# PonyProgFT.net
KiCad netlist of a schematic drawn in Altium Designer
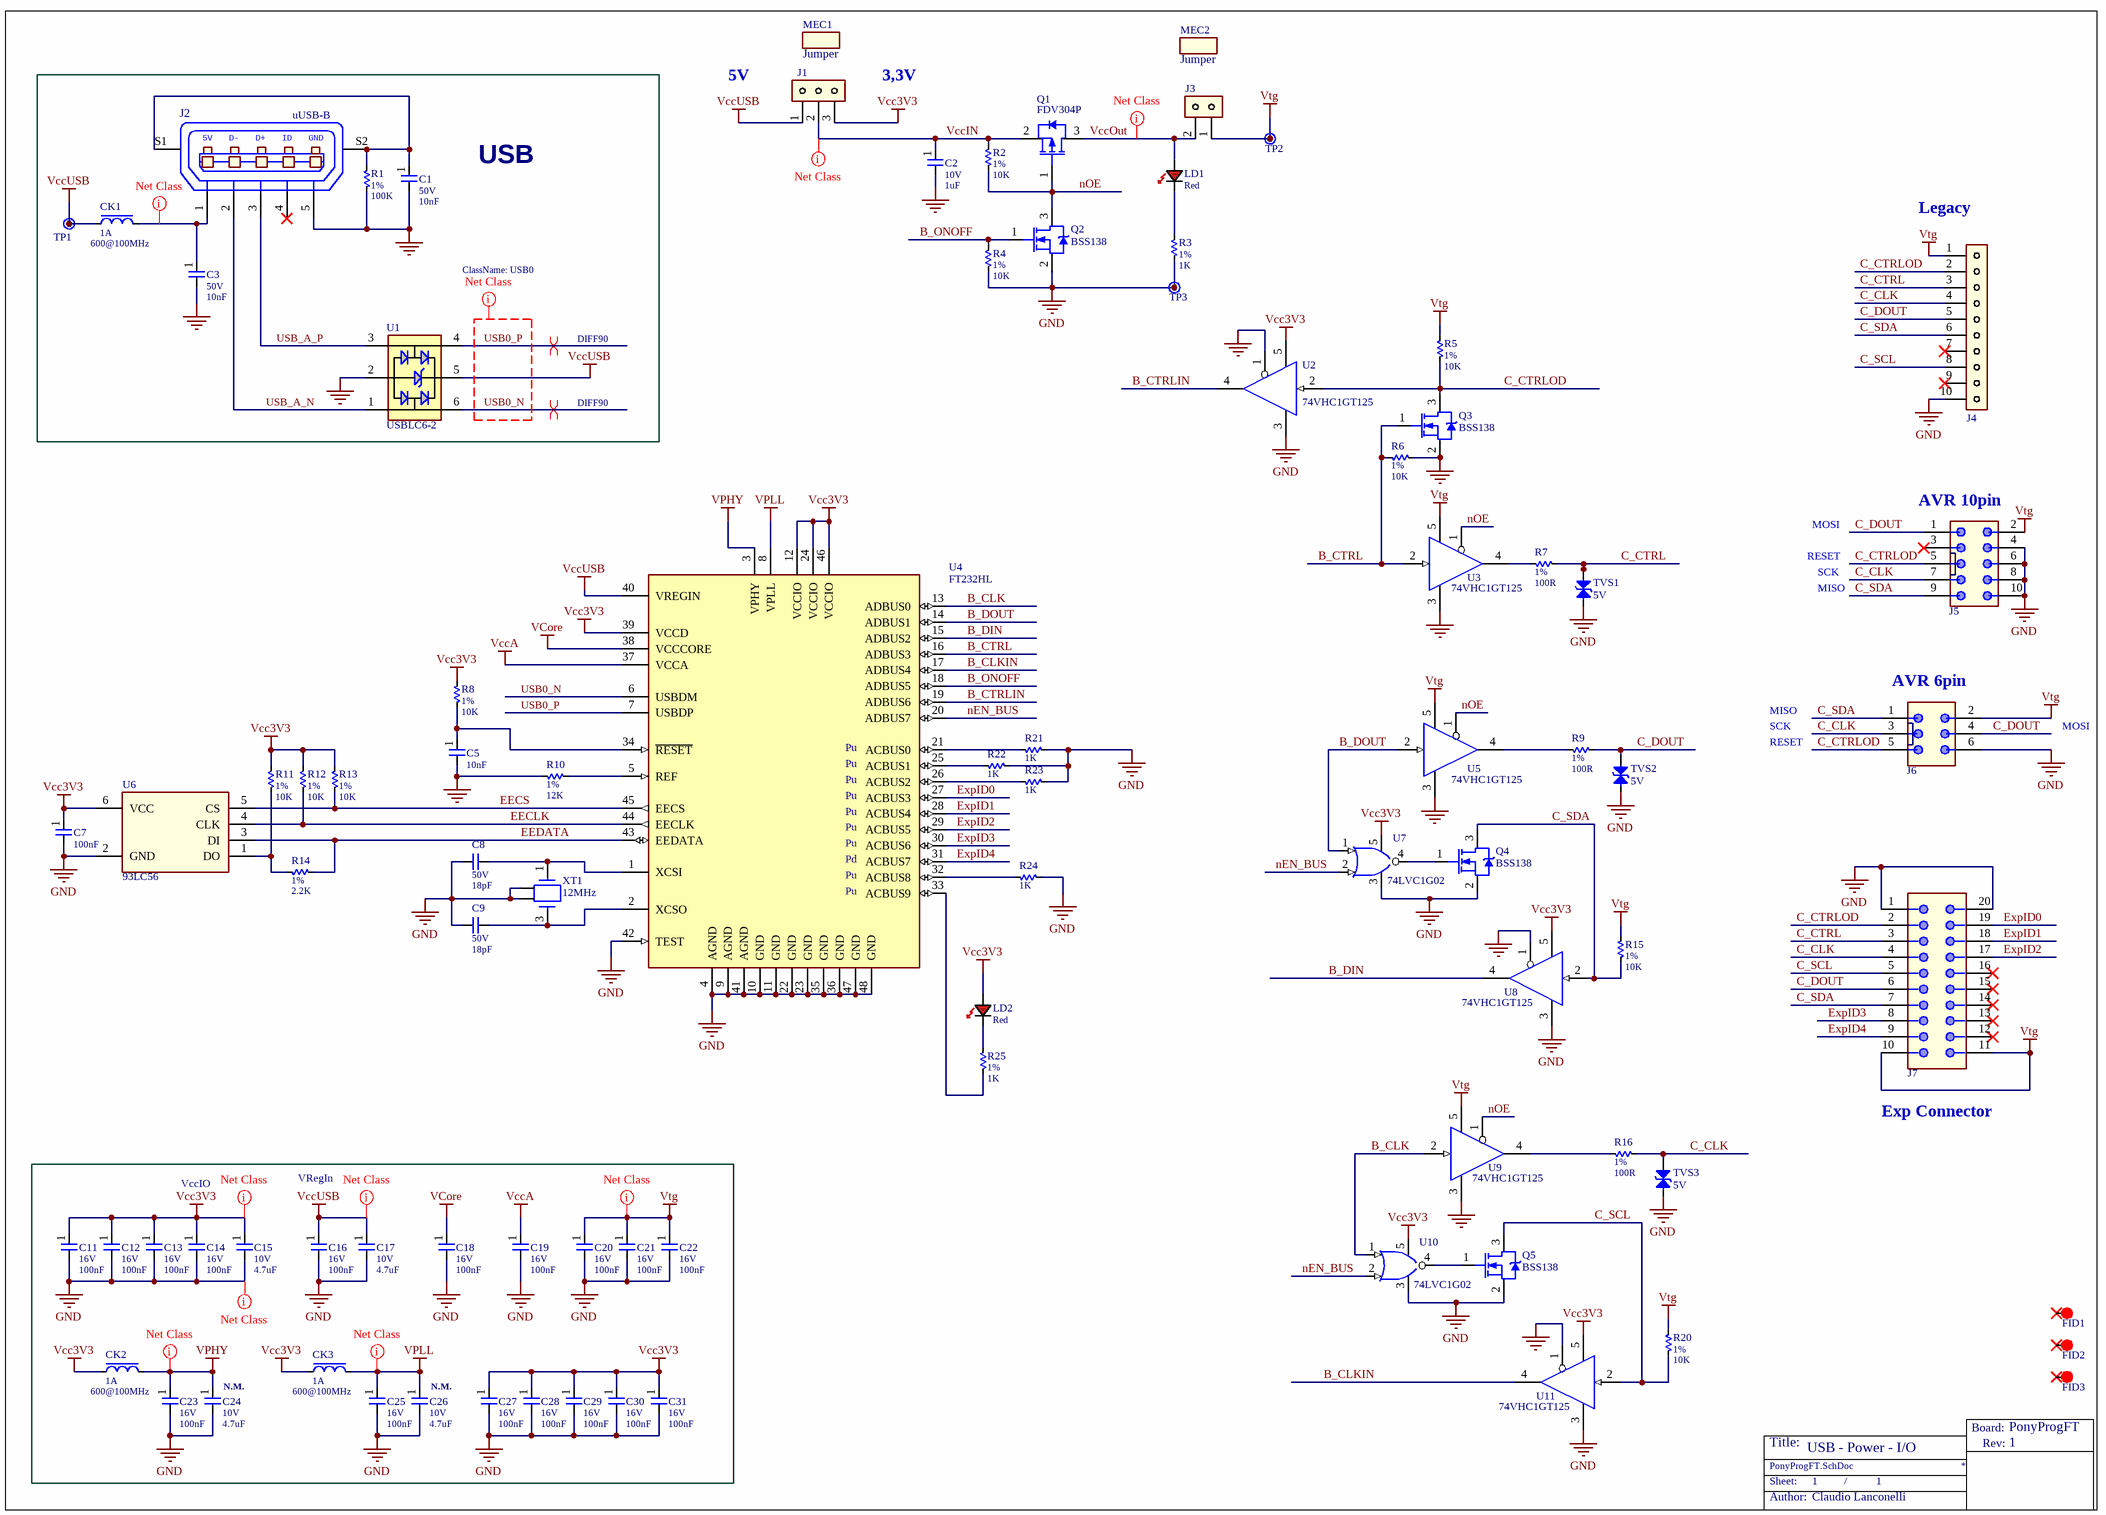
[diagram p0: PonyProgFT.SchDoc]

(export (version "E")
  (design (tool "Eeschema 10.0.6"))
  (components
    (comp (ref "C1")
      (value "10nF")
      (footprint "C0805_M")
      (description "Chip Ceramic Capacitor X7R 0805 10nF 50V 10%")
      (fields
        (field (name "TOLERANCE") "10%")
        (field (name "MANUFACTURER") "Samsung Electro-Mechanics")
        (field (name "VOLTAGE") "50V")
      )
      (libsource (lib "LancoLib") (part "CX7R10N50V10%0805_CL"))
    )
    (comp (ref "C2")
      (value "1uF")
      (footprint "C0603_M")
      (description "Chip Ceramic Capacitor X5R 0603 1uF 10V 10%")
      (fields
        (field (name "TOLERANCE") "10%")
        (field (name "MANUFACTURER") "Murata Electronics North America")
        (field (name "VOLTAGE") "10V")
      )
      (libsource (lib "LancoLib") (part "CX5R1U10V10%0603_GRM"))
    )
    (comp (ref "C3")
      (value "10nF")
      (footprint "C0805_M")
      (description "Chip Ceramic Capacitor X7R 0805 10nF 50V 10%")
      (fields
        (field (name "TOLERANCE") "10%")
        (field (name "MANUFACTURER") "Samsung Electro-Mechanics")
        (field (name "VOLTAGE") "50V")
      )
      (libsource (lib "LancoLib") (part "CX7R10N50V10%0805_CL"))
    )
    (comp (ref "C5")
      (value "10nF")
      (footprint "C0402_H")
      (description "Chip Ceramic Capacitor X7R 0402 10nF 25V 10%")
      (fields
        (field (name "TOLERANCE") "10%")
        (field (name "MANUFACTURER") "Murata Electronics North America")
      )
      (libsource (lib "LancoLib") (part "CX7R10N25V10%0402_GRM"))
    )
    (comp (ref "C7")
      (value "100nF")
      (footprint "C0402_H")
      (description "Chip Ceramic Capacitor X7R 0402 100nF 16V 10%")
      (fields
        (field (name "TOLERANCE") "10%")
        (field (name "MANUFACTURER") "Murata Electronics North America")
      )
      (libsource (lib "LancoLib") (part "CX7R100N16V10%0402_GRM"))
    )
    (comp (ref "C8")
      (value "18pF")
      (footprint "C0603_M")
      (description "Chip Ceramic Capacitor C0G 0603 18pF 50V 5%")
      (fields
        (field (name "TOLERANCE") "5%")
        (field (name "VOLTAGE") "50V")
        (field (name "MANUFACTURER") "Kemet")
      )
      (libsource (lib "LancoLib") (part "CCOG18P50V5%0603_KEMET"))
    )
    (comp (ref "C9")
      (value "18pF")
      (footprint "C0603_M")
      (description "Chip Ceramic Capacitor C0G 0603 18pF 50V 5%")
      (fields
        (field (name "TOLERANCE") "5%")
        (field (name "VOLTAGE") "50V")
        (field (name "MANUFACTURER") "Kemet")
      )
      (libsource (lib "LancoLib") (part "CCOG18P50V5%0603_KEMET"))
    )
    (comp (ref "C11")
      (value "100nF")
      (footprint "C0402_H")
      (description "Chip Ceramic Capacitor X7R 0402 100nF 16V 10%")
      (fields
        (field (name "TOLERANCE") "10%")
        (field (name "MANUFACTURER") "Murata Electronics North America")
        (field (name "VOLTAGE") "16V")
      )
      (libsource (lib "LancoLib") (part "CX7R100N16V10%0402_GRM"))
    )
    (comp (ref "C12")
      (value "100nF")
      (footprint "C0402_H")
      (description "Chip Ceramic Capacitor X7R 0402 100nF 16V 10%")
      (fields
        (field (name "TOLERANCE") "10%")
        (field (name "MANUFACTURER") "Murata Electronics North America")
        (field (name "VOLTAGE") "16V")
      )
      (libsource (lib "LancoLib") (part "CX7R100N16V10%0402_GRM"))
    )
    (comp (ref "C13")
      (value "100nF")
      (footprint "C0402_H")
      (description "Chip Ceramic Capacitor X7R 0402 100nF 16V 10%")
      (fields
        (field (name "TOLERANCE") "10%")
        (field (name "MANUFACTURER") "Murata Electronics North America")
        (field (name "VOLTAGE") "16V")
      )
      (libsource (lib "LancoLib") (part "CX7R100N16V10%0402_GRM"))
    )
    (comp (ref "C14")
      (value "100nF")
      (footprint "C0402_H")
      (description "Chip Ceramic Capacitor X7R 0402 100nF 16V 10%")
      (fields
        (field (name "TOLERANCE") "10%")
        (field (name "MANUFACTURER") "Murata Electronics North America")
        (field (name "VOLTAGE") "16V")
      )
      (libsource (lib "LancoLib") (part "CX7R100N16V10%0402_GRM"))
    )
    (comp (ref "C15")
      (value "4.7uF")
      (footprint "C0603_H")
      (description "Chip Ceramic Capacitor X5R 0603 4.7uF 10V 10%")
      (fields
        (field (name "TOLERANCE") "10%")
        (field (name "MANUFACTURER") "TDK Corporation")
        (field (name "VOLTAGE") "10V")
      )
      (libsource (lib "LancoLib") (part "CX5R4.7U10V10%0603_TDK"))
    )
    (comp (ref "C16")
      (value "100nF")
      (footprint "C0402_H")
      (description "Chip Ceramic Capacitor X7R 0402 100nF 16V 10%")
      (fields
        (field (name "TOLERANCE") "10%")
        (field (name "MANUFACTURER") "Murata Electronics North America")
        (field (name "VOLTAGE") "16V")
      )
      (libsource (lib "LancoLib") (part "CX7R100N16V10%0402_GRM"))
    )
    (comp (ref "C17")
      (value "4.7uF")
      (footprint "C0603_H")
      (description "Chip Ceramic Capacitor X5R 0603 4.7uF 10V 10%")
      (fields
        (field (name "TOLERANCE") "10%")
        (field (name "MANUFACTURER") "TDK Corporation")
        (field (name "VOLTAGE") "10V")
      )
      (libsource (lib "LancoLib") (part "CX5R4.7U10V10%0603_TDK"))
    )
    (comp (ref "C18")
      (value "100nF")
      (footprint "C0402_H")
      (description "Chip Ceramic Capacitor X7R 0402 100nF 16V 10%")
      (fields
        (field (name "TOLERANCE") "10%")
        (field (name "MANUFACTURER") "Murata Electronics North America")
        (field (name "VOLTAGE") "16V")
      )
      (libsource (lib "LancoLib") (part "CX7R100N16V10%0402_GRM"))
    )
    (comp (ref "C19")
      (value "100nF")
      (footprint "C0402_H")
      (description "Chip Ceramic Capacitor X7R 0402 100nF 16V 10%")
      (fields
        (field (name "TOLERANCE") "10%")
        (field (name "MANUFACTURER") "Murata Electronics North America")
        (field (name "VOLTAGE") "16V")
      )
      (libsource (lib "LancoLib") (part "CX7R100N16V10%0402_GRM"))
    )
    (comp (ref "C20")
      (value "100nF")
      (footprint "C0402_H")
      (description "Chip Ceramic Capacitor X7R 0402 100nF 16V 10%")
      (fields
        (field (name "TOLERANCE") "10%")
        (field (name "MANUFACTURER") "Murata Electronics North America")
        (field (name "VOLTAGE") "16V")
      )
      (libsource (lib "LancoLib") (part "CX7R100N16V10%0402_GRM"))
    )
    (comp (ref "C21")
      (value "100nF")
      (footprint "C0402_H")
      (description "Chip Ceramic Capacitor X7R 0402 100nF 16V 10%")
      (fields
        (field (name "TOLERANCE") "10%")
        (field (name "MANUFACTURER") "Murata Electronics North America")
        (field (name "VOLTAGE") "16V")
      )
      (libsource (lib "LancoLib") (part "CX7R100N16V10%0402_GRM"))
    )
    (comp (ref "C22")
      (value "100nF")
      (footprint "C0402_H")
      (description "Chip Ceramic Capacitor X7R 0402 100nF 16V 10%")
      (fields
        (field (name "TOLERANCE") "10%")
        (field (name "MANUFACTURER") "Murata Electronics North America")
        (field (name "VOLTAGE") "16V")
      )
      (libsource (lib "LancoLib") (part "CX7R100N16V10%0402_GRM"))
    )
    (comp (ref "C23")
      (value "100nF")
      (footprint "C0402_H")
      (description "Chip Ceramic Capacitor X7R 0402 100nF 16V 10%")
      (fields
        (field (name "TOLERANCE") "10%")
        (field (name "MANUFACTURER") "Murata Electronics North America")
        (field (name "VOLTAGE") "16V")
      )
      (libsource (lib "LancoLib") (part "CX7R100N16V10%0402_GRM"))
    )
    (comp (ref "C24")
      (value "4.7uF")
      (footprint "C0603_H")
      (description "Chip Ceramic Capacitor X5R 0603 4.7uF 10V 10%")
      (fields
        (field (name "TOLERANCE") "10%")
        (field (name "MANUFACTURER") "TDK Corporation")
        (field (name "POPULATED") "N.M.")
        (field (name "VOLTAGE") "10V")
      )
      (libsource (lib "LancoLib") (part "CX5R4.7U10V10%0603_TDK"))
    )
    (comp (ref "C25")
      (value "100nF")
      (footprint "C0402_H")
      (description "Chip Ceramic Capacitor X7R 0402 100nF 16V 10%")
      (fields
        (field (name "TOLERANCE") "10%")
        (field (name "MANUFACTURER") "Murata Electronics North America")
        (field (name "VOLTAGE") "16V")
      )
      (libsource (lib "LancoLib") (part "CX7R100N16V10%0402_GRM"))
    )
    (comp (ref "C26")
      (value "4.7uF")
      (footprint "C0603_H")
      (description "Chip Ceramic Capacitor X5R 0603 4.7uF 10V 10%")
      (fields
        (field (name "TOLERANCE") "10%")
        (field (name "MANUFACTURER") "TDK Corporation")
        (field (name "POPULATED") "N.M.")
        (field (name "VOLTAGE") "10V")
      )
      (libsource (lib "LancoLib") (part "CX5R4.7U10V10%0603_TDK"))
    )
    (comp (ref "C27")
      (value "100nF")
      (footprint "C0402_H")
      (description "Chip Ceramic Capacitor X7R 0402 100nF 16V 10%")
      (fields
        (field (name "TOLERANCE") "10%")
        (field (name "MANUFACTURER") "Murata Electronics North America")
        (field (name "VOLTAGE") "16V")
      )
      (libsource (lib "LancoLib") (part "CX7R100N16V10%0402_GRM"))
    )
    (comp (ref "C28")
      (value "100nF")
      (footprint "C0402_H")
      (description "Chip Ceramic Capacitor X7R 0402 100nF 16V 10%")
      (fields
        (field (name "TOLERANCE") "10%")
        (field (name "MANUFACTURER") "Murata Electronics North America")
        (field (name "VOLTAGE") "16V")
      )
      (libsource (lib "LancoLib") (part "CX7R100N16V10%0402_GRM"))
    )
    (comp (ref "C29")
      (value "100nF")
      (footprint "C0402_H")
      (description "Chip Ceramic Capacitor X7R 0402 100nF 16V 10%")
      (fields
        (field (name "TOLERANCE") "10%")
        (field (name "MANUFACTURER") "Murata Electronics North America")
        (field (name "VOLTAGE") "16V")
      )
      (libsource (lib "LancoLib") (part "CX7R100N16V10%0402_GRM"))
    )
    (comp (ref "C30")
      (value "100nF")
      (footprint "C0402_H")
      (description "Chip Ceramic Capacitor X7R 0402 100nF 16V 10%")
      (fields
        (field (name "TOLERANCE") "10%")
        (field (name "MANUFACTURER") "Murata Electronics North America")
        (field (name "VOLTAGE") "16V")
      )
      (libsource (lib "LancoLib") (part "CX7R100N16V10%0402_GRM"))
    )
    (comp (ref "C31")
      (value "100nF")
      (footprint "C0402_H")
      (description "Chip Ceramic Capacitor X7R 0402 100nF 16V 10%")
      (fields
        (field (name "TOLERANCE") "10%")
        (field (name "MANUFACTURER") "Murata Electronics North America")
        (field (name "VOLTAGE") "16V")
      )
      (libsource (lib "LancoLib") (part "CX7R100N16V10%0402_GRM"))
    )
    (comp (ref "CK1")
      (value "600@100MHz")
      (footprint "C0603_M")
      (description "Ferrite Chip Beads SMD 0603 600@100MHz 1A")
      (fields
        (field (name "MANUFACTURER") "TDK Corporation")
        (field (name "TOLERANCE") "25 %")
        (field (name "RATEDCURRENT") "1A")
      )
      (libsource (lib "LancoLib") (part "FCB600Z1A0603MPZ"))
    )
    (comp (ref "CK2")
      (value "600@100MHz")
      (footprint "C0603_M")
      (description "Ferrite Chip Beads SMD 0603 600@100MHz 1A")
      (fields
        (field (name "MANUFACTURER") "TDK Corporation")
        (field (name "TOLERANCE") "25 %")
        (field (name "RATEDCURRENT") "1A")
      )
      (libsource (lib "LancoLib") (part "FCB600Z1A0603MPZ"))
    )
    (comp (ref "CK3")
      (value "600@100MHz")
      (footprint "C0603_M")
      (description "Ferrite Chip Beads SMD 0603 600@100MHz 1A")
      (fields
        (field (name "MANUFACTURER") "TDK Corporation")
        (field (name "TOLERANCE") "25 %")
        (field (name "RATEDCURRENT") "1A")
      )
      (libsource (lib "LancoLib") (part "FCB600Z1A0603MPZ"))
    )
    (comp (ref "FID1")
      (value "Fiducial")
      (footprint "FID_1MM")
      (description "Fiducial (non montare)")
      (libsource (lib "LancoLib") (part "FID"))
    )
    (comp (ref "FID2")
      (value "Fiducial")
      (footprint "FID_1MM")
      (description "Fiducial (non montare)")
      (libsource (lib "LancoLib") (part "FID"))
    )
    (comp (ref "FID3")
      (value "Fiducial")
      (footprint "FID_1MM")
      (description "Fiducial (non montare)")
      (libsource (lib "LancoLib") (part "FID"))
    )
    (comp (ref "J1")
      (value "61300311121")
      (footprint "CON_WE_61300311121")
      (description "THT Vertical Pin Header Male WR-PHD, Pitch 2.54 mm, Single Row, 3 pins")
      (fields (field (name "VOLTAGE") "250VAC") (field (name "MANUFACTURER") "WE"))
      (libsource (lib "LancoLib") (part "CON_WE_61300311121"))
    )
    (comp (ref "J2")
      (value "10118192-0001LF")
      (footprint "CON_FCI_10118192")
      (description "Micro-USB Type-B, right-angle, horizontal receptacle")
      (fields (field (name "MANUFACTURER") "FCI") (field (name "TYPE") "uUSB-B"))
      (libsource (lib "LancoLib") (part "CON_FCI_10118192-0001LF"))
    )
    (comp (ref "J3")
      (value "61300211121")
      (footprint "CON_WE_61300211121")
      (description "THT Vertical Pin Header Male WR-PHD, Pitch 2.54 mm, Single Row, 2 pins")
      (fields (field (name "VOLTAGE") "250VAC") (field (name "MANUFACTURER") "WE"))
      (libsource (lib "LancoLib") (part "CON_WE_61300211121"))
    )
    (comp (ref "J4")
      (value "75915-310LF")
      (footprint "CON_FCI_75915-310LF")
      (description "CONN RCPT 10POS 0.1 GOLD PCB")
      (fields (field (name "MANUFACTURER") "FCI"))
      (libsource (lib "LancoLib") (part "CON_FCI_75915-310LF"))
    )
    (comp (ref "J5")
      (value "61201021621")
      (footprint "CON_WE_61201021621")
      (description "Male Box Header WR-BHD, THT, Vertical, pitch 2.54 mm, 10 pins")
      (fields (field (name "VOLTAGE") "250Vac") (field (name "MANUFACTURER") "WE"))
      (libsource (lib "LancoLib") (part "CON_WE_61201021621"))
    )
    (comp (ref "J6")
      (value "61200621621")
      (footprint "CON_WE_61200621621")
      (description "Male Box Header WR-BHD, THT, Vertical, pitch 2.54 mm, 6 pins")
      (fields (field (name "VOLTAGE") "250V") (field (name "MANUFACTURER") "WE"))
      (libsource (lib "LancoLib") (part "CON_WE_61200621621"))
    )
    (comp (ref "J7")
      (value "10056847-101LF")
      (footprint "CON_FCI_10056847-101LF")
      (description "Connector edge dual female 20 pos, 0.8pitch")
      (fields (field (name "MANUFACTURER") "Amphenol ICC (FCI)"))
      (libsource (lib "LancoLib") (part "CON_FCI_10056847-101LF"))
    )
    (comp (ref "LD1")
      (value "Red")
      (footprint "LED_WL-SMCW_1206")
      (description "Chip LED SMD WL-SMCW, size 1206, Red, 2V, 140 deg, 150 mcd")
      (fields (field (name "MANUFACTURER") "Wurth Electronics Inc.") (field (name "VOLTAGE") "2V"))
      (libsource (lib "LancoLib") (part "LED_WE_150120RS75000"))
    )
    (comp (ref "LD2")
      (value "Red")
      (footprint "LED_WL-SMCW_1206")
      (description "Chip LED SMD WL-SMCW, size 1206, Red, 2V, 140 deg, 150 mcd")
      (fields (field (name "MANUFACTURER") "Wurth Electronics Inc.") (field (name "VOLTAGE") "2V"))
      (libsource (lib "LancoLib") (part "LED_WE_150120RS75000"))
    )
    (comp (ref "MEC1")
      (value "Jumper")
      (description "Jumper with pullback, 2.54mm pitch, black")
      (fields (field (name "MANUFACTURER") "WE"))
      (libsource (lib "LancoLib") (part "MEC___"))
    )
    (comp (ref "MEC2")
      (value "Jumper")
      (description "Jumper with pullback, 2.54mm pitch, black")
      (fields (field (name "MANUFACTURER") "WE"))
      (libsource (lib "LancoLib") (part "MEC___"))
    )
    (comp (ref "Q1")
      (value "FDV304P")
      (footprint "SOT23-3_H")
      (description "IC MOSFET P-CH 25V 460mA SOT-23")
      (fields (field (name "MANUFACTURER") "On Semiconductor") (field (name "MAN_PN") "FDV304P"))
      (libsource (lib "LancoLib") (part "IC_FDV304P"))
    )
    (comp (ref "Q2")
      (value "BSS138")
      (footprint "SOT23-3_H")
      (description "MOSFET N-CH 50V 0.22A SOT-23")
      (fields
        (field (name "MANUFACTURER") "Fairchild Semiconductor")
        (field (name "VOLTAGE") "50V")
        (field (name "SERIE") "BSS138")
      )
      (libsource (lib "LancoLib") (part "IC_BSS138"))
    )
    (comp (ref "Q3")
      (value "BSS138")
      (footprint "SOT23-3_H")
      (description "MOSFET N-CH 50V 0.22A SOT-23")
      (fields
        (field (name "MANUFACTURER") "Fairchild Semiconductor")
        (field (name "VOLTAGE") "50V")
        (field (name "SERIE") "BSS138")
      )
      (libsource (lib "LancoLib") (part "IC_BSS138"))
    )
    (comp (ref "Q4")
      (value "BSS138")
      (footprint "SOT23-3_H")
      (description "MOSFET N-CH 50V 0.22A SOT-23")
      (fields
        (field (name "MANUFACTURER") "Fairchild Semiconductor")
        (field (name "VOLTAGE") "50V")
        (field (name "SERIE") "BSS138")
      )
      (libsource (lib "LancoLib") (part "IC_BSS138"))
    )
    (comp (ref "Q5")
      (value "BSS138")
      (footprint "SOT23-3_H")
      (description "MOSFET N-CH 50V 0.22A SOT-23")
      (fields
        (field (name "MANUFACTURER") "Fairchild Semiconductor")
        (field (name "VOLTAGE") "50V")
        (field (name "SERIE") "BSS138")
      )
      (libsource (lib "LancoLib") (part "IC_BSS138"))
    )
    (comp (ref "R1")
      (value "100K")
      (footprint "C0603_M")
      (description "Chip Resistor 0603 100K 1% 100ppm")
      (fields
        (field (name "VOLTAGE") "75V")
        (field (name "MANUFACTURER") "Vishay Dale")
        (field (name "TOLERANCE") "1%")
      )
      (libsource (lib "LancoLib") (part "CRES100K1%100P0603T_CRCW"))
    )
    (comp (ref "R2")
      (value "10K")
      (footprint "C0603_M")
      (description "Chip Resistor 0603 10K 1% 100ppm")
      (fields
        (field (name "VOLTAGE") "75V")
        (field (name "MANUFACTURER") "Vishay Dale")
        (field (name "TOLERANCE") "1%")
      )
      (libsource (lib "LancoLib") (part "CRES10K1%100P0603T_CRCW"))
    )
    (comp (ref "R3")
      (value "1K")
      (footprint "C0603_M")
      (description "Chip Resistor 0603 1K 1% 100ppm")
      (fields
        (field (name "VOLTAGE") "75V")
        (field (name "MANUFACTURER") "Vishay Dale")
        (field (name "TOLERANCE") "1%")
      )
      (libsource (lib "LancoLib") (part "CRES1K1%100P0603T_CRCW"))
    )
    (comp (ref "R4")
      (value "10K")
      (footprint "C0603_M")
      (description "Chip Resistor 0603 10K 1% 100ppm")
      (fields
        (field (name "VOLTAGE") "75V")
        (field (name "MANUFACTURER") "Vishay Dale")
        (field (name "TOLERANCE") "1%")
      )
      (libsource (lib "LancoLib") (part "CRES10K1%100P0603T_CRCW"))
    )
    (comp (ref "R5")
      (value "10K")
      (footprint "C0603_M")
      (description "Chip Resistor 0603 10K 1% 100ppm")
      (fields
        (field (name "VOLTAGE") "75V")
        (field (name "MANUFACTURER") "Vishay Dale")
        (field (name "TOLERANCE") "1%")
      )
      (libsource (lib "LancoLib") (part "CRES10K1%100P0603T_CRCW"))
    )
    (comp (ref "R6")
      (value "10K")
      (footprint "C0603_M")
      (description "Chip Resistor 0603 10K 1% 100ppm")
      (fields
        (field (name "VOLTAGE") "75V")
        (field (name "MANUFACTURER") "Vishay Dale")
        (field (name "TOLERANCE") "1%")
      )
      (libsource (lib "LancoLib") (part "CRES10K1%100P0603T_CRCW"))
    )
    (comp (ref "R7")
      (value "100R")
      (footprint "C0603_M")
      (description "Chip Resistor 0603 100R 1% 100ppm")
      (fields
        (field (name "VOLTAGE") "75V")
        (field (name "MANUFACTURER") "Vishay Dale")
        (field (name "TOLERANCE") "1%")
      )
      (libsource (lib "LancoLib") (part "CRES100R1%100P0603T_CRCW"))
    )
    (comp (ref "R8")
      (value "10K")
      (footprint "C0603_M")
      (description "Chip Resistor 0603 10K 1% 100ppm")
      (fields
        (field (name "VOLTAGE") "75V")
        (field (name "MANUFACTURER") "Vishay Dale")
        (field (name "TOLERANCE") "1%")
      )
      (libsource (lib "LancoLib") (part "CRES10K1%100P0603T_CRCW"))
    )
    (comp (ref "R9")
      (value "100R")
      (footprint "C0603_M")
      (description "Chip Resistor 0603 100R 1% 100ppm")
      (fields
        (field (name "VOLTAGE") "75V")
        (field (name "MANUFACTURER") "Vishay Dale")
        (field (name "TOLERANCE") "1%")
      )
      (libsource (lib "LancoLib") (part "CRES100R1%100P0603T_CRCW"))
    )
    (comp (ref "R10")
      (value "12K")
      (footprint "C0603_M")
      (description "Chip Resistor 0603 12K 1% 100ppm")
      (fields
        (field (name "VOLTAGE") "75V")
        (field (name "MANUFACTURER") "Vishay")
        (field (name "TOLERANCE") "1%")
      )
      (libsource (lib "LancoLib") (part "CRES12K1%100P0603T_CRCW"))
    )
    (comp (ref "R11")
      (value "10K")
      (footprint "C0603_M")
      (description "Chip Resistor 0603 10K 1% 100ppm")
      (fields
        (field (name "VOLTAGE") "75V")
        (field (name "MANUFACTURER") "Vishay Dale")
        (field (name "TOLERANCE") "1%")
      )
      (libsource (lib "LancoLib") (part "CRES10K1%100P0603T_CRCW"))
    )
    (comp (ref "R12")
      (value "10K")
      (footprint "C0603_M")
      (description "Chip Resistor 0603 10K 1% 100ppm")
      (fields
        (field (name "VOLTAGE") "75V")
        (field (name "MANUFACTURER") "Vishay Dale")
        (field (name "TOLERANCE") "1%")
      )
      (libsource (lib "LancoLib") (part "CRES10K1%100P0603T_CRCW"))
    )
    (comp (ref "R13")
      (value "10K")
      (footprint "C0603_M")
      (description "Chip Resistor 0603 10K 1% 100ppm")
      (fields
        (field (name "VOLTAGE") "75V")
        (field (name "MANUFACTURER") "Vishay Dale")
        (field (name "TOLERANCE") "1%")
      )
      (libsource (lib "LancoLib") (part "CRES10K1%100P0603T_CRCW"))
    )
    (comp (ref "R14")
      (value "2.2K")
      (footprint "C0402_H")
      (description "Chip Resistor 0402 2.2K 1% 100ppm")
      (fields
        (field (name "VOLTAGE") "50V")
        (field (name "MANUFACTURER") "Vishay Dale")
        (field (name "TOLERANCE") "1%")
      )
      (libsource (lib "LancoLib") (part "CRES2.2K1%100P0402U_CRCW"))
    )
    (comp (ref "R15")
      (value "10K")
      (footprint "C0603_M")
      (description "Chip Resistor 0603 10K 1% 100ppm")
      (fields
        (field (name "VOLTAGE") "75V")
        (field (name "MANUFACTURER") "Vishay Dale")
        (field (name "TOLERANCE") "1%")
      )
      (libsource (lib "LancoLib") (part "CRES10K1%100P0603T_CRCW"))
    )
    (comp (ref "R16")
      (value "100R")
      (footprint "C0603_M")
      (description "Chip Resistor 0603 100R 1% 100ppm")
      (fields
        (field (name "VOLTAGE") "75V")
        (field (name "MANUFACTURER") "Vishay Dale")
        (field (name "TOLERANCE") "1%")
      )
      (libsource (lib "LancoLib") (part "CRES100R1%100P0603T_CRCW"))
    )
    (comp (ref "R20")
      (value "10K")
      (footprint "C0603_M")
      (description "Chip Resistor 0603 10K 1% 100ppm")
      (fields
        (field (name "VOLTAGE") "75V")
        (field (name "MANUFACTURER") "Vishay Dale")
        (field (name "TOLERANCE") "1%")
      )
      (libsource (lib "LancoLib") (part "CRES10K1%100P0603T_CRCW"))
    )
    (comp (ref "R21")
      (value "1K")
      (footprint "C0603_M")
      (description "Chip Resistor 0603 1K 1% 100ppm")
      (fields (field (name "VOLTAGE") "75V") (field (name "MANUFACTURER") "Vishay Dale"))
      (libsource (lib "LancoLib") (part "CRES1K1%100P0603T_CRCW"))
    )
    (comp (ref "R22")
      (value "1K")
      (footprint "C0603_M")
      (description "Chip Resistor 0603 1K 1% 100ppm")
      (fields (field (name "VOLTAGE") "75V") (field (name "MANUFACTURER") "Vishay Dale"))
      (libsource (lib "LancoLib") (part "CRES1K1%100P0603T_CRCW"))
    )
    (comp (ref "R23")
      (value "1K")
      (footprint "C0603_M")
      (description "Chip Resistor 0603 1K 1% 100ppm")
      (fields (field (name "VOLTAGE") "75V") (field (name "MANUFACTURER") "Vishay Dale"))
      (libsource (lib "LancoLib") (part "CRES1K1%100P0603T_CRCW"))
    )
    (comp (ref "R24")
      (value "1K")
      (footprint "C0603_M")
      (description "Chip Resistor 0603 1K 1% 100ppm")
      (fields (field (name "VOLTAGE") "75V") (field (name "MANUFACTURER") "Vishay Dale"))
      (libsource (lib "LancoLib") (part "CRES1K1%100P0603T_CRCW"))
    )
    (comp (ref "R25")
      (value "1K")
      (footprint "C0603_M")
      (description "Chip Resistor 0603 1K 1% 100ppm")
      (fields
        (field (name "VOLTAGE") "75V")
        (field (name "MANUFACTURER") "Vishay Dale")
        (field (name "TOLERANCE") "1%")
      )
      (libsource (lib "LancoLib") (part "CRES1K1%100P0603T_CRCW"))
    )
    (comp (ref "TP1")
      (value "non montare")
      (footprint "TP-1MM")
      (description "Test Point, D=1mm (Foro 0.5mm), non montare")
      (libsource (lib "LancoLib") (part "TP_TPH-1MM"))
    )
    (comp (ref "TP2")
      (value "non montare")
      (footprint "TP-1MM")
      (description "Test Point, D=1mm (Foro 0.5mm), non montare")
      (libsource (lib "LancoLib") (part "TP_TPH-1MM"))
    )
    (comp (ref "TP3")
      (value "non montare")
      (footprint "TP-1MM")
      (description "Test Point, D=1mm (Foro 0.5mm), non montare")
      (libsource (lib "LancoLib") (part "TP_TPH-1MM"))
    )
    (comp (ref "TVS1")
      (value "82356050560")
      (footprint "C0603_M")
      (description "Chip ESD suppressor bidirectional 5V 0603")
      (fields (field (name "MANUFACTURER") "WE") (field (name "VOLTAGE") "5V"))
      (libsource (lib "LancoLib") (part "TVSP_WE-82356050560"))
    )
    (comp (ref "TVS2")
      (value "82356050560")
      (footprint "C0603_M")
      (description "Chip ESD suppressor bidirectional 5V 0603")
      (fields (field (name "MANUFACTURER") "WE") (field (name "VOLTAGE") "5V"))
      (libsource (lib "LancoLib") (part "TVSP_WE-82356050560"))
    )
    (comp (ref "TVS3")
      (value "82356050560")
      (footprint "C0603_M")
      (description "Chip ESD suppressor bidirectional 5V 0603")
      (fields (field (name "MANUFACTURER") "WE") (field (name "VOLTAGE") "5V"))
      (libsource (lib "LancoLib") (part "TVSP_WE-82356050560"))
    )
    (comp (ref "U1")
      (value "USBLC6-2P6")
      (footprint "SOT-666_M")
      (description "TVS 2 line, Low cap, 5V, SOT666")
      (fields
        (field (name "MANUFACTURER") "STMicroelectronics")
        (field (name "VOLTAGE") "5V")
        (field (name "SERIES") "USBLC6-2")
      )
      (libsource (lib "LancoLib") (part "IC_USBLC6-2P6"))
    )
    (comp (ref "U2")
      (value "M74VHC1GT125DT1G")
      (footprint "TSOP5-ON")
      (description "IC BUFFER NON-INVERT 5.5V 5-TSOP")
      (fields (field (name "MANUFACTURER") "ON Semiconductor") (field (name "SERIE") "74VHC1GT125"))
      (libsource (lib "LancoLib") (part "IC_M74VHC1GT125DT"))
    )
    (comp (ref "U3")
      (value "M74VHC1GT125DT1G")
      (footprint "TSOP5-ON")
      (description "IC BUFFER NON-INVERT 5.5V 5-TSOP")
      (fields (field (name "MANUFACTURER") "ON Semiconductor") (field (name "SERIE") "74VHC1GT125"))
      (libsource (lib "LancoLib") (part "IC_M74VHC1GT125DT"))
    )
    (comp (ref "U4")
      (value "FT232HL")
      (footprint "LQFP48_P50_M-STM")
      (description "IC HS USB TO UART/FIFO 48LQFP")
      (fields (field (name "MANUFACTURER") "FTDI") (field (name "MAN_PN") "FT232HL"))
      (libsource (lib "LancoLib") (part "IC_FT232HL"))
    )
    (comp (ref "U5")
      (value "M74VHC1GT125DT1G")
      (footprint "TSOP5-ON")
      (description "IC BUFFER NON-INVERT 5.5V 5-TSOP")
      (fields (field (name "MANUFACTURER") "ON Semiconductor") (field (name "SERIE") "74VHC1GT125"))
      (libsource (lib "LancoLib") (part "IC_M74VHC1GT125DT"))
    )
    (comp (ref "U6")
      (value "93LC56BT-I/OT")
      (footprint "SOT23-6_M")
      (description "IC EEPROM 2K SPI 2MHz SOT23-6")
      (fields (field (name "MANUFACTURER") "Microchip") (field (name "SERIE") "93LC56"))
      (libsource (lib "LancoLib") (part "IC_93LC56BT-I/OT"))
    )
    (comp (ref "U7")
      (value "74LVC1G02")
      (footprint "SOT23-5_M")
      (description "IC GATE NOR 1CH 2-INP 5-TSOP")
      (fields (field (name "MANUFACTURER") "NXP Semiconductors") (field (name "Comment") "74LVC1G02GV,125"))
      (libsource (lib "LancoLib") (part "IC_74LVC1G02GV"))
    )
    (comp (ref "U8")
      (value "M74VHC1GT125DT1G")
      (footprint "TSOP5-ON")
      (description "IC BUFFER NON-INVERT 5.5V 5-TSOP")
      (fields (field (name "MANUFACTURER") "ON Semiconductor") (field (name "SERIE") "74VHC1GT125"))
      (libsource (lib "LancoLib") (part "IC_M74VHC1GT125DT"))
    )
    (comp (ref "U9")
      (value "M74VHC1GT125DT1G")
      (footprint "TSOP5-ON")
      (description "IC BUFFER NON-INVERT 5.5V 5-TSOP")
      (fields (field (name "MANUFACTURER") "ON Semiconductor") (field (name "SERIE") "74VHC1GT125"))
      (libsource (lib "LancoLib") (part "IC_M74VHC1GT125DT"))
    )
    (comp (ref "U10")
      (value "74LVC1G02")
      (footprint "SOT23-5_M")
      (description "IC GATE NOR 1CH 2-INP 5-TSOP")
      (fields (field (name "MANUFACTURER") "NXP Semiconductors") (field (name "Comment") "74LVC1G02GV,125"))
      (libsource (lib "LancoLib") (part "IC_74LVC1G02GV"))
    )
    (comp (ref "U11")
      (value "M74VHC1GT125DT1G")
      (footprint "TSOP5-ON")
      (description "IC BUFFER NON-INVERT 5.5V 5-TSOP")
      (fields (field (name "MANUFACTURER") "ON Semiconductor") (field (name "SERIE") "74VHC1GT125"))
      (libsource (lib "LancoLib") (part "IC_M74VHC1GT125DT"))
    )
    (comp (ref "XT1")
      (value "12MHz")
      (footprint "XTAL-NX3225SA")
      (description "Xtal SMD 12MHz 8pF 25ppm (-40 to 85)")
      (fields (field (name "TOLERANCE") "25ppm") (field (name "MANUFACTURER") "NDK"))
      (libsource (lib "LancoLib") (part "XTAL_NX3225SA-12MHZ-STD-CSR-6"))
    )
  )
  (nets
    (net (code "1") (name "/B_CLK") (class "Default")
      (node (ref "U10") (pin "1") (pinfunction "A_1") (pintype "input"))
      (node (ref "U4") (pin "13") (pinfunction "ADBUS0_13") (pintype "bidirectional"))
      (node (ref "U9") (pin "2") (pinfunction "A_2") (pintype "input"))
    )
    (net (code "2") (name "/B_CLKIN") (class "Default")
      (node (ref "U11") (pin "4") (pinfunction "Y_4") (pintype "passive"))
      (node (ref "U4") (pin "17") (pinfunction "ADBUS4_17") (pintype "bidirectional"))
    )
    (net (code "3") (name "/B_CTRL") (class "Default")
      (node (ref "Q3") (pin "1") (pinfunction "G_1") (pintype "passive"))
      (node (ref "R6") (pin "1") (pintype "passive"))
      (node (ref "U3") (pin "2") (pinfunction "A_2") (pintype "input"))
      (node (ref "U4") (pin "16") (pinfunction "ADBUS3_16") (pintype "bidirectional"))
    )
    (net (code "4") (name "/B_CTRLIN") (class "Default")
      (node (ref "U2") (pin "4") (pinfunction "Y_4") (pintype "passive"))
      (node (ref "U4") (pin "19") (pinfunction "ADBUS6_19") (pintype "bidirectional"))
    )
    (net (code "5") (name "/B_DIN") (class "Default")
      (node (ref "U4") (pin "15") (pinfunction "ADBUS2_15") (pintype "bidirectional"))
      (node (ref "U8") (pin "4") (pinfunction "Y_4") (pintype "passive"))
    )
    (net (code "6") (name "/B_DOUT") (class "Default")
      (node (ref "U4") (pin "14") (pinfunction "ADBUS1_14") (pintype "bidirectional"))
      (node (ref "U5") (pin "2") (pinfunction "A_2") (pintype "input"))
      (node (ref "U7") (pin "1") (pinfunction "A_1") (pintype "input"))
    )
    (net (code "7") (name "/B_ONOFF") (class "Default")
      (node (ref "Q2") (pin "1") (pinfunction "G_1") (pintype "passive"))
      (node (ref "R4") (pin "1") (pintype "passive"))
      (node (ref "U4") (pin "18") (pinfunction "ADBUS5_18") (pintype "bidirectional"))
    )
    (net (code "8") (name "/C_CLK") (class "Default")
      (node (ref "J4") (pin "4") (pinfunction "4_4") (pintype "passive"))
      (node (ref "J5") (pin "7") (pinfunction "7_7") (pintype "passive"))
      (node (ref "J6") (pin "3") (pinfunction "3_3") (pintype "passive"))
      (node (ref "J7") (pin "4") (pinfunction "4_4") (pintype "passive"))
      (node (ref "R16") (pin "2") (pintype "passive"))
      (node (ref "TVS3") (pin "2") (pintype "passive"))
    )
    (net (code "9") (name "/C_CTRL") (class "Default")
      (node (ref "J4") (pin "3") (pinfunction "3_3") (pintype "passive"))
      (node (ref "J7") (pin "3") (pinfunction "3_3") (pintype "passive"))
      (node (ref "R7") (pin "2") (pintype "passive"))
      (node (ref "TVS1") (pin "2") (pintype "passive"))
    )
    (net (code "10") (name "/C_CTRLOD") (class "Default")
      (node (ref "J4") (pin "2") (pinfunction "2_2") (pintype "passive"))
      (node (ref "J5") (pin "5") (pinfunction "5_5") (pintype "passive"))
      (node (ref "J6") (pin "5") (pinfunction "5_5") (pintype "passive"))
      (node (ref "J7") (pin "2") (pinfunction "2_2") (pintype "passive"))
      (node (ref "Q3") (pin "3") (pinfunction "D_3") (pintype "passive"))
      (node (ref "R5") (pin "2") (pintype "passive"))
      (node (ref "U2") (pin "2") (pinfunction "A_2") (pintype "input"))
    )
    (net (code "11") (name "/C_DOUT") (class "Default")
      (node (ref "J4") (pin "5") (pinfunction "5_5") (pintype "passive"))
      (node (ref "J5") (pin "1") (pinfunction "1_1") (pintype "passive"))
      (node (ref "J6") (pin "4") (pinfunction "4_4") (pintype "passive"))
      (node (ref "J7") (pin "6") (pinfunction "6_6") (pintype "passive"))
      (node (ref "R9") (pin "2") (pintype "passive"))
      (node (ref "TVS2") (pin "2") (pintype "passive"))
    )
    (net (code "12") (name "/C_SCL") (class "Default")
      (node (ref "J4") (pin "8") (pinfunction "8_8") (pintype "passive"))
      (node (ref "J7") (pin "5") (pinfunction "5_5") (pintype "passive"))
      (node (ref "Q5") (pin "3") (pinfunction "D_3") (pintype "passive"))
      (node (ref "R20") (pin "2") (pintype "passive"))
      (node (ref "U11") (pin "2") (pinfunction "A_2") (pintype "input"))
    )
    (net (code "13") (name "/C_SDA") (class "Default")
      (node (ref "J4") (pin "6") (pinfunction "6_6") (pintype "passive"))
      (node (ref "J5") (pin "9") (pinfunction "9_9") (pintype "passive"))
      (node (ref "J6") (pin "1") (pinfunction "1_1") (pintype "passive"))
      (node (ref "J7") (pin "7") (pinfunction "7_7") (pintype "passive"))
      (node (ref "Q4") (pin "3") (pinfunction "D_3") (pintype "passive"))
      (node (ref "R15") (pin "1") (pintype "passive"))
      (node (ref "U8") (pin "2") (pinfunction "A_2") (pintype "input"))
    )
    (net (code "14") (name "/EECLK") (class "Default")
      (node (ref "R12") (pin "2") (pintype "passive"))
      (node (ref "U4") (pin "44") (pinfunction "EECLK_44") (pintype "output"))
      (node (ref "U6") (pin "4") (pinfunction "CLK_4") (pintype "passive"))
    )
    (net (code "15") (name "/EECS") (class "Default")
      (node (ref "R13") (pin "2") (pintype "passive"))
      (node (ref "U4") (pin "45") (pinfunction "EECS_45") (pintype "output"))
      (node (ref "U6") (pin "5") (pinfunction "CS_5") (pintype "passive"))
    )
    (net (code "16") (name "/EEDATA") (class "Default")
      (node (ref "R14") (pin "2") (pintype "passive"))
      (node (ref "U4") (pin "43") (pinfunction "EEDATA_43") (pintype "bidirectional"))
      (node (ref "U6") (pin "3") (pinfunction "DI_3") (pintype "passive"))
    )
    (net (code "17") (name "/ExpID0") (class "Default")
      (node (ref "J7") (pin "19") (pinfunction "19_19") (pintype "passive"))
      (node (ref "U4") (pin "27") (pinfunction "ACBUS3_27") (pintype "bidirectional"))
    )
    (net (code "18") (name "/ExpID1") (class "Default")
      (node (ref "J7") (pin "18") (pinfunction "18_18") (pintype "passive"))
      (node (ref "U4") (pin "28") (pinfunction "ACBUS4_28") (pintype "bidirectional"))
    )
    (net (code "19") (name "/ExpID2") (class "Default")
      (node (ref "J7") (pin "17") (pinfunction "17_17") (pintype "passive"))
      (node (ref "U4") (pin "29") (pinfunction "ACBUS5_29") (pintype "bidirectional"))
    )
    (net (code "20") (name "/ExpID3") (class "Default")
      (node (ref "J7") (pin "8") (pinfunction "8_8") (pintype "passive"))
      (node (ref "U4") (pin "30") (pinfunction "ACBUS6_30") (pintype "bidirectional"))
    )
    (net (code "21") (name "/ExpID4") (class "Default")
      (node (ref "J7") (pin "9") (pinfunction "9_9") (pintype "passive"))
      (node (ref "U4") (pin "31") (pinfunction "ACBUS7_31") (pintype "bidirectional"))
    )
    (net (code "22") (name "/USB0_N") (class "Default")
      (node (ref "U1") (pin "6") (pinfunction "6_6") (pintype "passive"))
      (node (ref "U4") (pin "6") (pinfunction "USBDM_6") (pintype "passive"))
    )
    (net (code "23") (name "/USB0_P") (class "Default")
      (node (ref "U1") (pin "4") (pinfunction "4_4") (pintype "passive"))
      (node (ref "U4") (pin "7") (pinfunction "USBDP_7") (pintype "passive"))
    )
    (net (code "24") (name "/USB_A_N") (class "Default")
      (node (ref "J2") (pin "2") (pinfunction "P2_2") (pintype "passive"))
      (node (ref "U1") (pin "1") (pinfunction "1_1") (pintype "passive"))
    )
    (net (code "25") (name "/USB_A_P") (class "Default")
      (node (ref "J2") (pin "3") (pinfunction "P3_3") (pintype "passive"))
      (node (ref "U1") (pin "3") (pinfunction "3_3") (pintype "passive"))
    )
    (net (code "26") (name "/VccIN") (class "Default")
      (node (ref "C2") (pin "1") (pintype "passive"))
      (node (ref "J1") (pin "2") (pinfunction "2_2") (pintype "passive"))
      (node (ref "Q1") (pin "2") (pinfunction "S_2") (pintype "passive"))
      (node (ref "R2") (pin "1") (pintype "passive"))
    )
    (net (code "27") (name "/VccOut") (class "Default")
      (node (ref "J3") (pin "2") (pinfunction "2_2") (pintype "passive"))
      (node (ref "LD1") (pin "A") (pinfunction "Anode_A") (pintype "passive"))
      (node (ref "Q1") (pin "3") (pinfunction "D_3") (pintype "passive"))
    )
    (net (code "28") (name "/nEN_BUS") (class "Default")
      (node (ref "U10") (pin "2") (pinfunction "B_2") (pintype "input"))
      (node (ref "U4") (pin "20") (pinfunction "ADBUS7_20") (pintype "bidirectional"))
      (node (ref "U7") (pin "2") (pinfunction "B_2") (pintype "input"))
    )
    (net (code "29") (name "/nOE") (class "Default")
      (node (ref "Q1") (pin "1") (pinfunction "G_1") (pintype "passive"))
      (node (ref "Q2") (pin "3") (pinfunction "D_3") (pintype "passive"))
      (node (ref "R2") (pin "2") (pintype "passive"))
      (node (ref "U3") (pin "1") (pinfunction "~{OE}_1") (pintype "passive"))
      (node (ref "U5") (pin "1") (pinfunction "~{OE}_1") (pintype "passive"))
      (node (ref "U9") (pin "1") (pinfunction "~{OE}_1") (pintype "passive"))
    )
    (net (code "30") (name "GND") (class "Default")
      (node (ref "C1") (pin "2") (pintype "passive"))
      (node (ref "C11") (pin "2") (pintype "passive"))
      (node (ref "C12") (pin "2") (pintype "passive"))
      (node (ref "C13") (pin "2") (pintype "passive"))
      (node (ref "C14") (pin "2") (pintype "passive"))
      (node (ref "C15") (pin "2") (pintype "passive"))
      (node (ref "C16") (pin "2") (pintype "passive"))
      (node (ref "C17") (pin "2") (pintype "passive"))
      (node (ref "C18") (pin "2") (pintype "passive"))
      (node (ref "C19") (pin "2") (pintype "passive"))
      (node (ref "C2") (pin "2") (pintype "passive"))
      (node (ref "C20") (pin "2") (pintype "passive"))
      (node (ref "C21") (pin "2") (pintype "passive"))
      (node (ref "C22") (pin "2") (pintype "passive"))
      (node (ref "C23") (pin "2") (pintype "passive"))
      (node (ref "C24") (pin "2") (pintype "passive"))
      (node (ref "C25") (pin "2") (pintype "passive"))
      (node (ref "C26") (pin "2") (pintype "passive"))
      (node (ref "C27") (pin "2") (pintype "passive"))
      (node (ref "C28") (pin "2") (pintype "passive"))
      (node (ref "C29") (pin "2") (pintype "passive"))
      (node (ref "C3") (pin "2") (pintype "passive"))
      (node (ref "C30") (pin "2") (pintype "passive"))
      (node (ref "C31") (pin "2") (pintype "passive"))
      (node (ref "C5") (pin "2") (pintype "passive"))
      (node (ref "C7") (pin "2") (pintype "passive"))
      (node (ref "C8") (pin "1") (pintype "passive"))
      (node (ref "C9") (pin "1") (pintype "passive"))
      (node (ref "J2") (pin "5") (pinfunction "P5_5") (pintype "passive"))
      (node (ref "J4") (pin "10") (pinfunction "10_10") (pintype "passive"))
      (node (ref "J5") (pin "10") (pinfunction "10_10") (pintype "passive"))
      (node (ref "J5") (pin "4") (pinfunction "4_4") (pintype "passive"))
      (node (ref "J5") (pin "6") (pinfunction "6_6") (pintype "passive"))
      (node (ref "J5") (pin "8") (pinfunction "8_8") (pintype "passive"))
      (node (ref "J6") (pin "6") (pinfunction "6_6") (pintype "passive"))
      (node (ref "J7") (pin "1") (pinfunction "1_1") (pintype "passive"))
      (node (ref "J7") (pin "20") (pinfunction "20_20") (pintype "passive"))
      (node (ref "Q2") (pin "2") (pinfunction "S_2") (pintype "passive"))
      (node (ref "Q3") (pin "2") (pinfunction "S_2") (pintype "passive"))
      (node (ref "Q4") (pin "2") (pinfunction "S_2") (pintype "passive"))
      (node (ref "Q5") (pin "2") (pinfunction "S_2") (pintype "passive"))
      (node (ref "R1") (pin "2") (pintype "passive"))
      (node (ref "R10") (pin "1") (pintype "passive"))
      (node (ref "R21") (pin "1") (pintype "passive"))
      (node (ref "R22") (pin "1") (pintype "passive"))
      (node (ref "R23") (pin "1") (pintype "passive"))
      (node (ref "R24") (pin "1") (pintype "passive"))
      (node (ref "R3") (pin "2") (pintype "passive"))
      (node (ref "R4") (pin "2") (pintype "passive"))
      (node (ref "R6") (pin "2") (pintype "passive"))
      (node (ref "TP3") (pin "1") (pinfunction "TP_1") (pintype "passive"))
      (node (ref "TVS1") (pin "1") (pintype "passive"))
      (node (ref "TVS2") (pin "1") (pintype "passive"))
      (node (ref "TVS3") (pin "1") (pintype "passive"))
      (node (ref "U1") (pin "2") (pinfunction "2_2") (pintype "passive"))
      (node (ref "U10") (pin "3") (pinfunction "GND_3") (pintype "power_in"))
      (node (ref "U11") (pin "1") (pinfunction "~{OE}_1") (pintype "passive"))
      (node (ref "U11") (pin "3") (pinfunction "GND_3") (pintype "power_in"))
      (node (ref "U2") (pin "1") (pinfunction "~{OE}_1") (pintype "passive"))
      (node (ref "U2") (pin "3") (pinfunction "GND_3") (pintype "power_in"))
      (node (ref "U3") (pin "3") (pinfunction "GND_3") (pintype "power_in"))
      (node (ref "U4") (pin "10") (pinfunction "GND_10") (pintype "power_in"))
      (node (ref "U4") (pin "11") (pinfunction "GND_11") (pintype "power_in"))
      (node (ref "U4") (pin "22") (pinfunction "GND_22") (pintype "power_in"))
      (node (ref "U4") (pin "23") (pinfunction "GND_23") (pintype "power_in"))
      (node (ref "U4") (pin "35") (pinfunction "GND_35") (pintype "power_in"))
      (node (ref "U4") (pin "36") (pinfunction "GND_36") (pintype "power_in"))
      (node (ref "U4") (pin "4") (pinfunction "AGND_4") (pintype "power_in"))
      (node (ref "U4") (pin "41") (pinfunction "AGND_41") (pintype "power_in"))
      (node (ref "U4") (pin "42") (pinfunction "TEST_42") (pintype "input"))
      (node (ref "U4") (pin "47") (pinfunction "GND_47") (pintype "power_in"))
      (node (ref "U4") (pin "48") (pinfunction "GND_48") (pintype "power_in"))
      (node (ref "U4") (pin "9") (pinfunction "AGND_9") (pintype "power_in"))
      (node (ref "U5") (pin "3") (pinfunction "GND_3") (pintype "power_in"))
      (node (ref "U6") (pin "2") (pinfunction "GND_2") (pintype "power_in"))
      (node (ref "U7") (pin "3") (pinfunction "GND_3") (pintype "power_in"))
      (node (ref "U8") (pin "1") (pinfunction "~{OE}_1") (pintype "passive"))
      (node (ref "U8") (pin "3") (pinfunction "GND_3") (pintype "power_in"))
      (node (ref "U9") (pin "3") (pinfunction "GND_3") (pintype "power_in"))
      (node (ref "XT1") (pin "2") (pinfunction "GND_2") (pintype "passive"))
      (node (ref "XT1") (pin "4") (pinfunction "GND_4") (pintype "power_in"))
    )
    (net (code "31") (name "Net-(J2-P1)") (class "Default")
      (node (ref "C3") (pin "1") (pintype "passive"))
      (node (ref "CK1") (pin "2") (pintype "passive"))
      (node (ref "J2") (pin "1") (pinfunction "P1_1") (pintype "passive"))
    )
    (net (code "32") (name "Net-(J2-Shell1)") (class "Default")
      (node (ref "C1") (pin "1") (pintype "passive"))
      (node (ref "J2") (pin "S1") (pinfunction "Shell1_S1") (pintype "passive"))
      (node (ref "J2") (pin "S2") (pinfunction "Shell2_S2") (pintype "passive"))
      (node (ref "R1") (pin "1") (pintype "passive"))
    )
    (net (code "33") (name "Net-(LD1-Cathode)") (class "Default")
      (node (ref "LD1") (pin "K") (pinfunction "Cathode_K") (pintype "passive"))
      (node (ref "R3") (pin "1") (pintype "passive"))
    )
    (net (code "34") (name "Net-(LD2-Cathode)") (class "Default")
      (node (ref "LD2") (pin "K") (pinfunction "Cathode_K") (pintype "passive"))
      (node (ref "R25") (pin "2") (pintype "passive"))
    )
    (net (code "35") (name "Net-(Q4-G)") (class "Default")
      (node (ref "Q4") (pin "1") (pinfunction "G_1") (pintype "passive"))
      (node (ref "U7") (pin "4") (pinfunction "Y_4") (pintype "passive"))
    )
    (net (code "36") (name "Net-(Q5-G)") (class "Default")
      (node (ref "Q5") (pin "1") (pinfunction "G_1") (pintype "passive"))
      (node (ref "U10") (pin "4") (pinfunction "Y_4") (pintype "passive"))
    )
    (net (code "37") (name "Net-(U3-Y)") (class "Default")
      (node (ref "R7") (pin "1") (pintype "passive"))
      (node (ref "U3") (pin "4") (pinfunction "Y_4") (pintype "passive"))
    )
    (net (code "38") (name "Net-(U4-ACBUS0)") (class "Default")
      (node (ref "R21") (pin "2") (pintype "passive"))
      (node (ref "U4") (pin "21") (pinfunction "ACBUS0_21") (pintype "bidirectional"))
    )
    (net (code "39") (name "Net-(U4-ACBUS1)") (class "Default")
      (node (ref "R22") (pin "2") (pintype "passive"))
      (node (ref "U4") (pin "25") (pinfunction "ACBUS1_25") (pintype "bidirectional"))
    )
    (net (code "40") (name "Net-(U4-ACBUS2)") (class "Default")
      (node (ref "R23") (pin "2") (pintype "passive"))
      (node (ref "U4") (pin "26") (pinfunction "ACBUS2_26") (pintype "bidirectional"))
    )
    (net (code "41") (name "Net-(U4-ACBUS8)") (class "Default")
      (node (ref "R24") (pin "2") (pintype "passive"))
      (node (ref "U4") (pin "32") (pinfunction "ACBUS8_32") (pintype "bidirectional"))
    )
    (net (code "42") (name "Net-(U4-ACBUS9)") (class "Default")
      (node (ref "R25") (pin "1") (pintype "passive"))
      (node (ref "U4") (pin "33") (pinfunction "ACBUS9_33") (pintype "bidirectional"))
    )
    (net (code "43") (name "Net-(U4-REF)") (class "Default")
      (node (ref "R10") (pin "2") (pintype "passive"))
      (node (ref "U4") (pin "5") (pinfunction "REF_5") (pintype "input"))
    )
    (net (code "44") (name "Net-(U4-XCSI)") (class "Default")
      (node (ref "C8") (pin "2") (pintype "passive"))
      (node (ref "U4") (pin "1") (pinfunction "XCSI_1") (pintype "passive"))
      (node (ref "XT1") (pin "1") (pinfunction "1_1") (pintype "passive"))
    )
    (net (code "45") (name "Net-(U4-XCSO)") (class "Default")
      (node (ref "C9") (pin "2") (pintype "passive"))
      (node (ref "U4") (pin "2") (pinfunction "XCSO_2") (pintype "passive"))
      (node (ref "XT1") (pin "3") (pinfunction "3_3") (pintype "passive"))
    )
    (net (code "46") (name "Net-(U4-~{RESET})") (class "Default")
      (node (ref "C5") (pin "1") (pintype "passive"))
      (node (ref "R8") (pin "1") (pintype "passive"))
      (node (ref "U4") (pin "34") (pinfunction "~{RESET}_34") (pintype "input"))
    )
    (net (code "47") (name "Net-(U5-Y)") (class "Default")
      (node (ref "R9") (pin "1") (pintype "passive"))
      (node (ref "U5") (pin "4") (pinfunction "Y_4") (pintype "passive"))
    )
    (net (code "48") (name "Net-(U6-DO)") (class "Default")
      (node (ref "R11") (pin "2") (pintype "passive"))
      (node (ref "R14") (pin "1") (pintype "passive"))
      (node (ref "U6") (pin "1") (pinfunction "DO_1") (pintype "passive"))
    )
    (net (code "49") (name "Net-(U9-Y)") (class "Default")
      (node (ref "R16") (pin "1") (pintype "passive"))
      (node (ref "U9") (pin "4") (pinfunction "Y_4") (pintype "passive"))
    )
    (net (code "50") (name "VCore") (class "Default")
      (node (ref "C18") (pin "1") (pintype "passive"))
      (node (ref "U4") (pin "38") (pinfunction "VCCCORE_38") (pintype "power_in"))
    )
    (net (code "51") (name "VPHY") (class "Default")
      (node (ref "C23") (pin "1") (pintype "passive"))
      (node (ref "C24") (pin "1") (pintype "passive"))
      (node (ref "CK2") (pin "2") (pintype "passive"))
      (node (ref "U4") (pin "3") (pinfunction "VPHY_3") (pintype "power_in"))
    )
    (net (code "52") (name "VPLL") (class "Default")
      (node (ref "C25") (pin "1") (pintype "passive"))
      (node (ref "C26") (pin "1") (pintype "passive"))
      (node (ref "CK3") (pin "2") (pintype "passive"))
      (node (ref "U4") (pin "8") (pinfunction "VPLL_8") (pintype "power_in"))
    )
    (net (code "53") (name "Vcc3V3") (class "Default")
      (node (ref "C11") (pin "1") (pintype "passive"))
      (node (ref "C12") (pin "1") (pintype "passive"))
      (node (ref "C13") (pin "1") (pintype "passive"))
      (node (ref "C14") (pin "1") (pintype "passive"))
      (node (ref "C15") (pin "1") (pintype "passive"))
      (node (ref "C27") (pin "1") (pintype "passive"))
      (node (ref "C28") (pin "1") (pintype "passive"))
      (node (ref "C29") (pin "1") (pintype "passive"))
      (node (ref "C30") (pin "1") (pintype "passive"))
      (node (ref "C31") (pin "1") (pintype "passive"))
      (node (ref "C7") (pin "1") (pintype "passive"))
      (node (ref "CK2") (pin "1") (pintype "passive"))
      (node (ref "CK3") (pin "1") (pintype "passive"))
      (node (ref "J1") (pin "3") (pinfunction "3_3") (pintype "passive"))
      (node (ref "LD2") (pin "A") (pinfunction "Anode_A") (pintype "passive"))
      (node (ref "R11") (pin "1") (pintype "passive"))
      (node (ref "R12") (pin "1") (pintype "passive"))
      (node (ref "R13") (pin "1") (pintype "passive"))
      (node (ref "R8") (pin "2") (pintype "passive"))
      (node (ref "U10") (pin "5") (pinfunction "VCC_5") (pintype "power_in"))
      (node (ref "U11") (pin "5") (pinfunction "VCC_5") (pintype "power_in"))
      (node (ref "U2") (pin "5") (pinfunction "VCC_5") (pintype "power_in"))
      (node (ref "U4") (pin "12") (pinfunction "VCCIO_12") (pintype "power_in"))
      (node (ref "U4") (pin "24") (pinfunction "VCCIO_24") (pintype "power_in"))
      (node (ref "U4") (pin "39") (pinfunction "VCCD_39") (pintype "power_in"))
      (node (ref "U4") (pin "46") (pinfunction "VCCIO_46") (pintype "power_in"))
      (node (ref "U6") (pin "6") (pinfunction "VCC_6") (pintype "power_in"))
      (node (ref "U7") (pin "5") (pinfunction "VCC_5") (pintype "power_in"))
      (node (ref "U8") (pin "5") (pinfunction "VCC_5") (pintype "power_in"))
    )
    (net (code "54") (name "VccA") (class "Default")
      (node (ref "C19") (pin "1") (pintype "passive"))
      (node (ref "U4") (pin "37") (pinfunction "VCCA_37") (pintype "power_in"))
    )
    (net (code "55") (name "VccUSB") (class "Default")
      (node (ref "C16") (pin "1") (pintype "passive"))
      (node (ref "C17") (pin "1") (pintype "passive"))
      (node (ref "CK1") (pin "1") (pintype "passive"))
      (node (ref "J1") (pin "1") (pinfunction "1_1") (pintype "passive"))
      (node (ref "TP1") (pin "1") (pinfunction "TP_1") (pintype "passive"))
      (node (ref "U1") (pin "5") (pinfunction "5_5") (pintype "passive"))
      (node (ref "U4") (pin "40") (pinfunction "VREGIN_40") (pintype "power_in"))
    )
    (net (code "56") (name "Vtg") (class "Default")
      (node (ref "C20") (pin "1") (pintype "passive"))
      (node (ref "C21") (pin "1") (pintype "passive"))
      (node (ref "C22") (pin "1") (pintype "passive"))
      (node (ref "J3") (pin "1") (pinfunction "1_1") (pintype "passive"))
      (node (ref "J4") (pin "1") (pinfunction "1_1") (pintype "passive"))
      (node (ref "J5") (pin "2") (pinfunction "2_2") (pintype "passive"))
      (node (ref "J6") (pin "2") (pinfunction "2_2") (pintype "passive"))
      (node (ref "J7") (pin "10") (pinfunction "10_10") (pintype "passive"))
      (node (ref "J7") (pin "11") (pinfunction "11_11") (pintype "passive"))
      (node (ref "R15") (pin "2") (pintype "passive"))
      (node (ref "R20") (pin "1") (pintype "passive"))
      (node (ref "R5") (pin "1") (pintype "passive"))
      (node (ref "TP2") (pin "1") (pinfunction "TP_1") (pintype "passive"))
      (node (ref "U3") (pin "5") (pinfunction "VCC_5") (pintype "power_in"))
      (node (ref "U5") (pin "5") (pinfunction "VCC_5") (pintype "power_in"))
      (node (ref "U9") (pin "5") (pinfunction "VCC_5") (pintype "power_in"))
    )
    (net (code "57") (name "unconnected-(FID1-Pad1)") (class "Default")
      (node (ref "FID1") (pin "1") (pinfunction "1_1") (pintype "passive+no_connect"))
    )
    (net (code "58") (name "unconnected-(FID2-Pad1)") (class "Default")
      (node (ref "FID2") (pin "1") (pinfunction "1_1") (pintype "passive+no_connect"))
    )
    (net (code "59") (name "unconnected-(FID3-Pad1)") (class "Default")
      (node (ref "FID3") (pin "1") (pinfunction "1_1") (pintype "passive+no_connect"))
    )
    (net (code "60") (name "unconnected-(J2-P4-Pad4)") (class "Default")
      (node (ref "J2") (pin "4") (pinfunction "P4_4") (pintype "passive+no_connect"))
    )
    (net (code "61") (name "unconnected-(J4-Pad7)") (class "Default")
      (node (ref "J4") (pin "7") (pinfunction "7_7") (pintype "passive+no_connect"))
    )
    (net (code "62") (name "unconnected-(J4-Pad9)") (class "Default")
      (node (ref "J4") (pin "9") (pinfunction "9_9") (pintype "passive+no_connect"))
    )
    (net (code "63") (name "unconnected-(J5-Pad3)") (class "Default")
      (node (ref "J5") (pin "3") (pinfunction "3_3") (pintype "passive+no_connect"))
    )
    (net (code "64") (name "unconnected-(J7-Pad12)") (class "Default")
      (node (ref "J7") (pin "12") (pinfunction "12_12") (pintype "passive+no_connect"))
    )
    (net (code "65") (name "unconnected-(J7-Pad13)") (class "Default")
      (node (ref "J7") (pin "13") (pinfunction "13_13") (pintype "passive+no_connect"))
    )
    (net (code "66") (name "unconnected-(J7-Pad14)") (class "Default")
      (node (ref "J7") (pin "14") (pinfunction "14_14") (pintype "passive+no_connect"))
    )
    (net (code "67") (name "unconnected-(J7-Pad15)") (class "Default")
      (node (ref "J7") (pin "15") (pinfunction "15_15") (pintype "passive+no_connect"))
    )
    (net (code "68") (name "unconnected-(J7-Pad16)") (class "Default")
      (node (ref "J7") (pin "16") (pinfunction "16_16") (pintype "passive+no_connect"))
    )
  )
)
